# rel-rflag.net
KiCad netlist of a schematic drawn in EAGLE
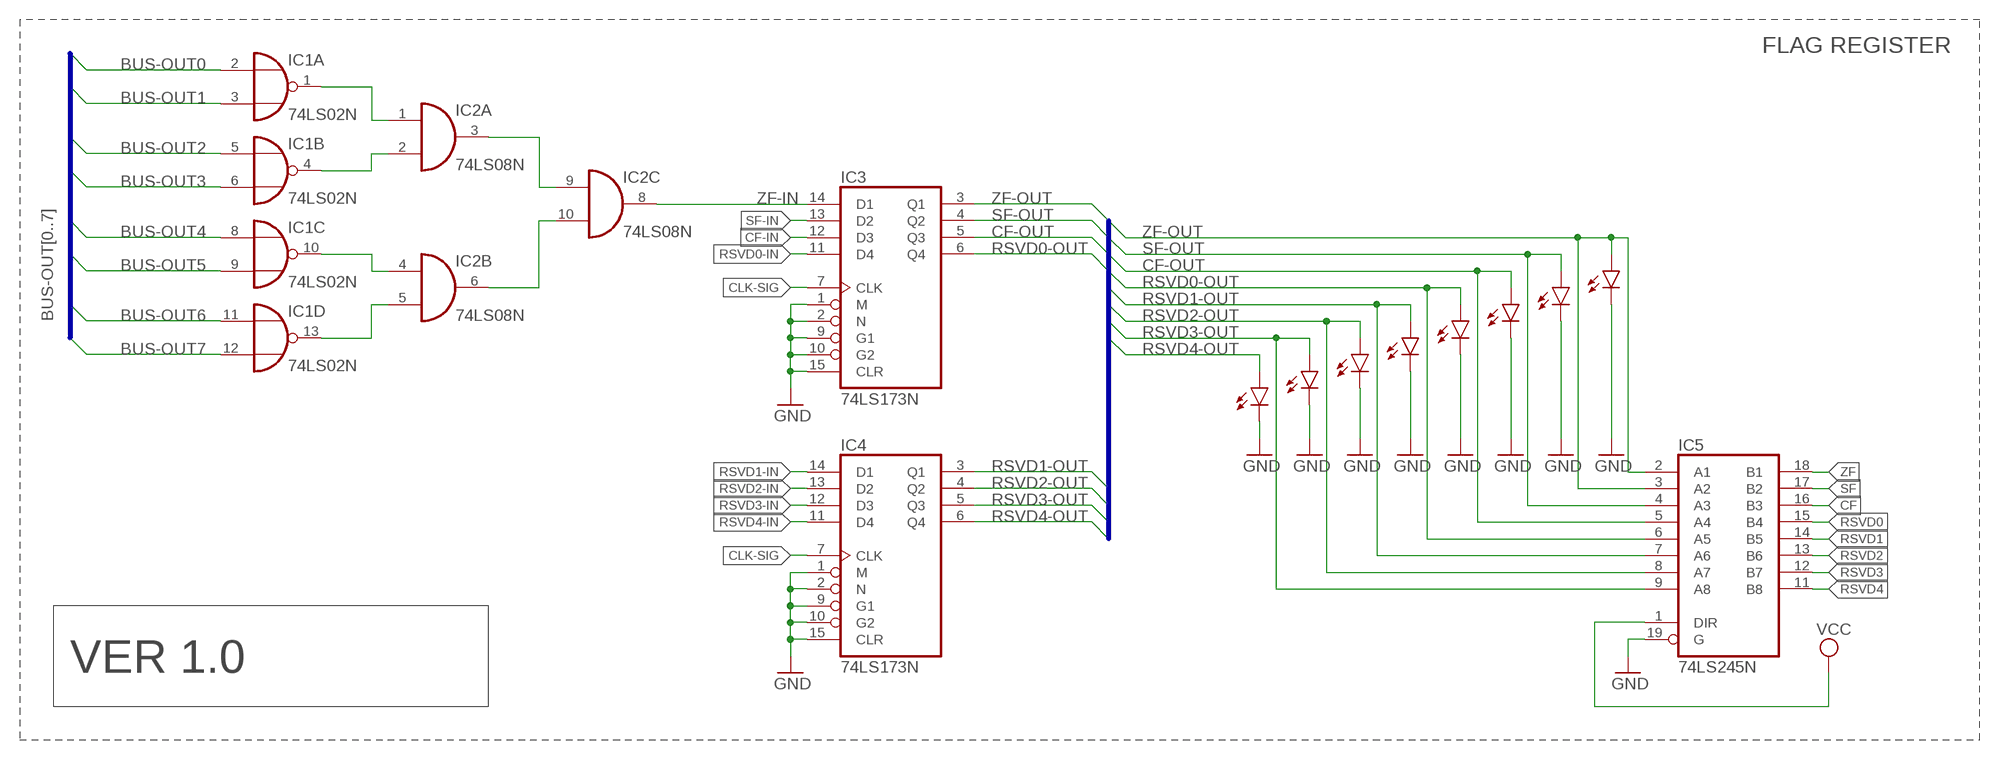
[diagram p0: schematic, sheet 1]

(export (version "E")
  (design (tool "Eeschema 10.0.6"))
  (components
    (comp (ref "IC1")
      (value "74LS02N")
      (footprint "eagle-import:DIL14")
      (libsource (lib "eagle-import") (part "7402NLS"))
    )
    (comp (ref "IC2")
      (value "74LS08N")
      (footprint "eagle-import:DIL14")
      (libsource (lib "eagle-import") (part "7408NLS"))
    )
    (comp (ref "IC3")
      (value "74LS173N")
      (footprint "eagle-import:DIL16")
      (libsource (lib "eagle-import") (part "74173NLS"))
    )
    (comp (ref "IC4")
      (value "74LS173N")
      (footprint "eagle-import:DIL16")
      (libsource (lib "eagle-import") (part "74173NLS"))
    )
    (comp (ref "IC5")
      (value "74LS245N")
      (footprint "eagle-import:DIL20")
      (libsource (lib "eagle-import") (part "74245NLS"))
    )
    (comp (ref "LED1")
      (value "LED5MM")
      (footprint "eagle-import:LED5MM")
      (libsource (lib "eagle-import") (part "LED5MM"))
    )
    (comp (ref "LED2")
      (value "LED5MM")
      (footprint "eagle-import:LED5MM")
      (libsource (lib "eagle-import") (part "LED5MM"))
    )
    (comp (ref "LED3")
      (value "LED5MM")
      (footprint "eagle-import:LED5MM")
      (libsource (lib "eagle-import") (part "LED5MM"))
    )
    (comp (ref "LED4")
      (value "LED5MM")
      (footprint "eagle-import:LED5MM")
      (libsource (lib "eagle-import") (part "LED5MM"))
    )
    (comp (ref "LED5")
      (value "LED5MM")
      (footprint "eagle-import:LED5MM")
      (libsource (lib "eagle-import") (part "LED5MM"))
    )
    (comp (ref "LED6")
      (value "LED5MM")
      (footprint "eagle-import:LED5MM")
      (libsource (lib "eagle-import") (part "LED5MM"))
    )
    (comp (ref "LED7")
      (value "LED5MM")
      (footprint "eagle-import:LED5MM")
      (libsource (lib "eagle-import") (part "LED5MM"))
    )
    (comp (ref "LED8")
      (value "LED5MM")
      (footprint "eagle-import:LED5MM")
      (libsource (lib "eagle-import") (part "LED5MM"))
    )
  )
  (nets
    (net (code "1") (name "/BUS-OUT0") (class "Default")
      (node (ref "IC1") (pin "2") (pinfunction "I0_2") (pintype "input"))
    )
    (net (code "2") (name "/BUS-OUT1") (class "Default")
      (node (ref "IC1") (pin "3") (pinfunction "I1_3") (pintype "input"))
    )
    (net (code "3") (name "/BUS-OUT2") (class "Default")
      (node (ref "IC1") (pin "5") (pinfunction "I0_5") (pintype "input"))
    )
    (net (code "4") (name "/BUS-OUT3") (class "Default")
      (node (ref "IC1") (pin "6") (pinfunction "I1_6") (pintype "input"))
    )
    (net (code "5") (name "/BUS-OUT4") (class "Default")
      (node (ref "IC1") (pin "8") (pinfunction "I0_8") (pintype "input"))
    )
    (net (code "6") (name "/BUS-OUT5") (class "Default")
      (node (ref "IC1") (pin "9") (pinfunction "I1_9") (pintype "input"))
    )
    (net (code "7") (name "/BUS-OUT6") (class "Default")
      (node (ref "IC1") (pin "11") (pinfunction "I0_11") (pintype "input"))
    )
    (net (code "8") (name "/BUS-OUT7") (class "Default")
      (node (ref "IC1") (pin "12") (pinfunction "I1_12") (pintype "input"))
    )
    (net (code "10") (name "/CF-OUT") (class "Default")
      (node (ref "IC3") (pin "5") (pinfunction "Q3_5") (pintype "tri_state"))
      (node (ref "IC5") (pin "5") (pinfunction "A4_5") (pintype "bidirectional"))
      (node (ref "LED3") (pin "A") (pinfunction "A_A") (pintype "passive"))
    )
    (net (code "11") (name "/RSVD0-OUT") (class "Default")
      (node (ref "IC3") (pin "6") (pinfunction "Q4_6") (pintype "tri_state"))
      (node (ref "IC5") (pin "6") (pinfunction "A5_6") (pintype "bidirectional"))
      (node (ref "LED4") (pin "A") (pinfunction "A_A") (pintype "passive"))
    )
    (net (code "12") (name "/RSVD1-OUT") (class "Default")
      (node (ref "IC4") (pin "3") (pinfunction "Q1_3") (pintype "tri_state"))
      (node (ref "IC5") (pin "7") (pinfunction "A6_7") (pintype "bidirectional"))
      (node (ref "LED5") (pin "A") (pinfunction "A_A") (pintype "passive"))
    )
    (net (code "13") (name "/RSVD2-OUT") (class "Default")
      (node (ref "IC4") (pin "4") (pinfunction "Q2_4") (pintype "tri_state"))
      (node (ref "IC5") (pin "8") (pinfunction "A7_8") (pintype "bidirectional"))
      (node (ref "LED6") (pin "A") (pinfunction "A_A") (pintype "passive"))
    )
    (net (code "14") (name "/RSVD3-OUT") (class "Default")
      (node (ref "IC4") (pin "5") (pinfunction "Q3_5") (pintype "tri_state"))
      (node (ref "IC5") (pin "9") (pinfunction "A8_9") (pintype "bidirectional"))
      (node (ref "LED7") (pin "A") (pinfunction "A_A") (pintype "passive"))
    )
    (net (code "15") (name "/RSVD4-OUT") (class "Default")
      (node (ref "IC4") (pin "6") (pinfunction "Q4_6") (pintype "tri_state"))
      (node (ref "LED8") (pin "A") (pinfunction "A_A") (pintype "passive"))
    )
    (net (code "16") (name "/SF-OUT") (class "Default")
      (node (ref "IC3") (pin "4") (pinfunction "Q2_4") (pintype "tri_state"))
      (node (ref "IC5") (pin "4") (pinfunction "A3_4") (pintype "bidirectional"))
      (node (ref "LED2") (pin "A") (pinfunction "A_A") (pintype "passive"))
    )
    (net (code "17") (name "/ZF-IN") (class "Default")
      (node (ref "IC2") (pin "8") (pinfunction "O_8") (pintype "output"))
      (node (ref "IC3") (pin "14") (pinfunction "D1_14") (pintype "input"))
    )
    (net (code "18") (name "/ZF-OUT") (class "Default")
      (node (ref "IC3") (pin "3") (pinfunction "Q1_3") (pintype "tri_state"))
      (node (ref "IC5") (pin "2") (pinfunction "A1_2") (pintype "bidirectional"))
      (node (ref "IC5") (pin "3") (pinfunction "A2_3") (pintype "bidirectional"))
      (node (ref "LED1") (pin "A") (pinfunction "A_A") (pintype "passive"))
    )
    (net (code "19") (name "CF") (class "Default")
      (node (ref "IC5") (pin "16") (pinfunction "B3_16") (pintype "bidirectional"))
    )
    (net (code "20") (name "CF-IN") (class "Default")
      (node (ref "IC3") (pin "12") (pinfunction "D3_12") (pintype "input"))
    )
    (net (code "21") (name "CLK-SIG") (class "Default")
      (node (ref "IC3") (pin "7") (pinfunction "CLK_7") (pintype "input"))
      (node (ref "IC4") (pin "7") (pinfunction "CLK_7") (pintype "input"))
    )
    (net (code "22") (name "GND") (class "Default")
      (node (ref "IC3") (pin "1") (pinfunction "M_1") (pintype "input"))
      (node (ref "IC3") (pin "10") (pinfunction "G2_10") (pintype "input"))
      (node (ref "IC3") (pin "15") (pinfunction "CLR_15") (pintype "input"))
      (node (ref "IC3") (pin "2") (pinfunction "N_2") (pintype "input"))
      (node (ref "IC3") (pin "9") (pinfunction "G1_9") (pintype "input"))
      (node (ref "IC4") (pin "1") (pinfunction "M_1") (pintype "input"))
      (node (ref "IC4") (pin "10") (pinfunction "G2_10") (pintype "input"))
      (node (ref "IC4") (pin "15") (pinfunction "CLR_15") (pintype "input"))
      (node (ref "IC4") (pin "2") (pinfunction "N_2") (pintype "input"))
      (node (ref "IC4") (pin "9") (pinfunction "G1_9") (pintype "input"))
      (node (ref "IC5") (pin "19") (pinfunction "G_19") (pintype "input"))
      (node (ref "LED1") (pin "K") (pinfunction "C_K") (pintype "passive"))
      (node (ref "LED2") (pin "K") (pinfunction "C_K") (pintype "passive"))
      (node (ref "LED3") (pin "K") (pinfunction "C_K") (pintype "passive"))
      (node (ref "LED4") (pin "K") (pinfunction "C_K") (pintype "passive"))
      (node (ref "LED5") (pin "K") (pinfunction "C_K") (pintype "passive"))
      (node (ref "LED6") (pin "K") (pinfunction "C_K") (pintype "passive"))
      (node (ref "LED7") (pin "K") (pinfunction "C_K") (pintype "passive"))
      (node (ref "LED8") (pin "K") (pinfunction "C_K") (pintype "passive"))
    )
    (net (code "23") (name "Net-(IC1A-O)") (class "Default")
      (node (ref "IC1") (pin "1") (pinfunction "O_1") (pintype "output"))
      (node (ref "IC2") (pin "1") (pinfunction "I0_1") (pintype "input"))
    )
    (net (code "24") (name "Net-(IC1B-O)") (class "Default")
      (node (ref "IC1") (pin "4") (pinfunction "O_4") (pintype "output"))
      (node (ref "IC2") (pin "2") (pinfunction "I1_2") (pintype "input"))
    )
    (net (code "25") (name "Net-(IC1C-O)") (class "Default")
      (node (ref "IC1") (pin "10") (pinfunction "O_10") (pintype "output"))
      (node (ref "IC2") (pin "4") (pinfunction "I0_4") (pintype "input"))
    )
    (net (code "26") (name "Net-(IC1D-O)") (class "Default")
      (node (ref "IC1") (pin "13") (pinfunction "O_13") (pintype "output"))
      (node (ref "IC2") (pin "5") (pinfunction "I1_5") (pintype "input"))
    )
    (net (code "27") (name "Net-(IC2A-O)") (class "Default")
      (node (ref "IC2") (pin "3") (pinfunction "O_3") (pintype "output"))
      (node (ref "IC2") (pin "9") (pinfunction "I0_9") (pintype "input"))
    )
    (net (code "28") (name "Net-(IC2B-O)") (class "Default")
      (node (ref "IC2") (pin "10") (pinfunction "I1_10") (pintype "input"))
      (node (ref "IC2") (pin "6") (pinfunction "O_6") (pintype "output"))
    )
    (net (code "29") (name "RSVD0") (class "Default")
      (node (ref "IC5") (pin "15") (pinfunction "B4_15") (pintype "bidirectional"))
    )
    (net (code "30") (name "RSVD0-IN") (class "Default")
      (node (ref "IC3") (pin "11") (pinfunction "D4_11") (pintype "input"))
    )
    (net (code "31") (name "RSVD1") (class "Default")
      (node (ref "IC5") (pin "14") (pinfunction "B5_14") (pintype "bidirectional"))
    )
    (net (code "32") (name "RSVD1-IN") (class "Default")
      (node (ref "IC4") (pin "14") (pinfunction "D1_14") (pintype "input"))
    )
    (net (code "33") (name "RSVD2") (class "Default")
      (node (ref "IC5") (pin "13") (pinfunction "B6_13") (pintype "bidirectional"))
    )
    (net (code "34") (name "RSVD2-IN") (class "Default")
      (node (ref "IC4") (pin "13") (pinfunction "D2_13") (pintype "input"))
    )
    (net (code "35") (name "RSVD3") (class "Default")
      (node (ref "IC5") (pin "12") (pinfunction "B7_12") (pintype "bidirectional"))
    )
    (net (code "36") (name "RSVD3-IN") (class "Default")
      (node (ref "IC4") (pin "12") (pinfunction "D3_12") (pintype "input"))
    )
    (net (code "37") (name "RSVD4") (class "Default")
      (node (ref "IC5") (pin "11") (pinfunction "B8_11") (pintype "bidirectional"))
    )
    (net (code "38") (name "RSVD4-IN") (class "Default")
      (node (ref "IC4") (pin "11") (pinfunction "D4_11") (pintype "input"))
    )
    (net (code "39") (name "SF") (class "Default")
      (node (ref "IC5") (pin "17") (pinfunction "B2_17") (pintype "bidirectional"))
    )
    (net (code "40") (name "SF-IN") (class "Default")
      (node (ref "IC3") (pin "13") (pinfunction "D2_13") (pintype "input"))
    )
    (net (code "41") (name "VCC") (class "Default")
      (node (ref "IC5") (pin "1") (pinfunction "DIR_1") (pintype "input"))
    )
    (net (code "42") (name "ZF") (class "Default")
      (node (ref "IC5") (pin "18") (pinfunction "B1_18") (pintype "bidirectional"))
    )
  )
)
